# SENSOR_BOARD.net
KiCad netlist of a schematic drawn in Altium Designer
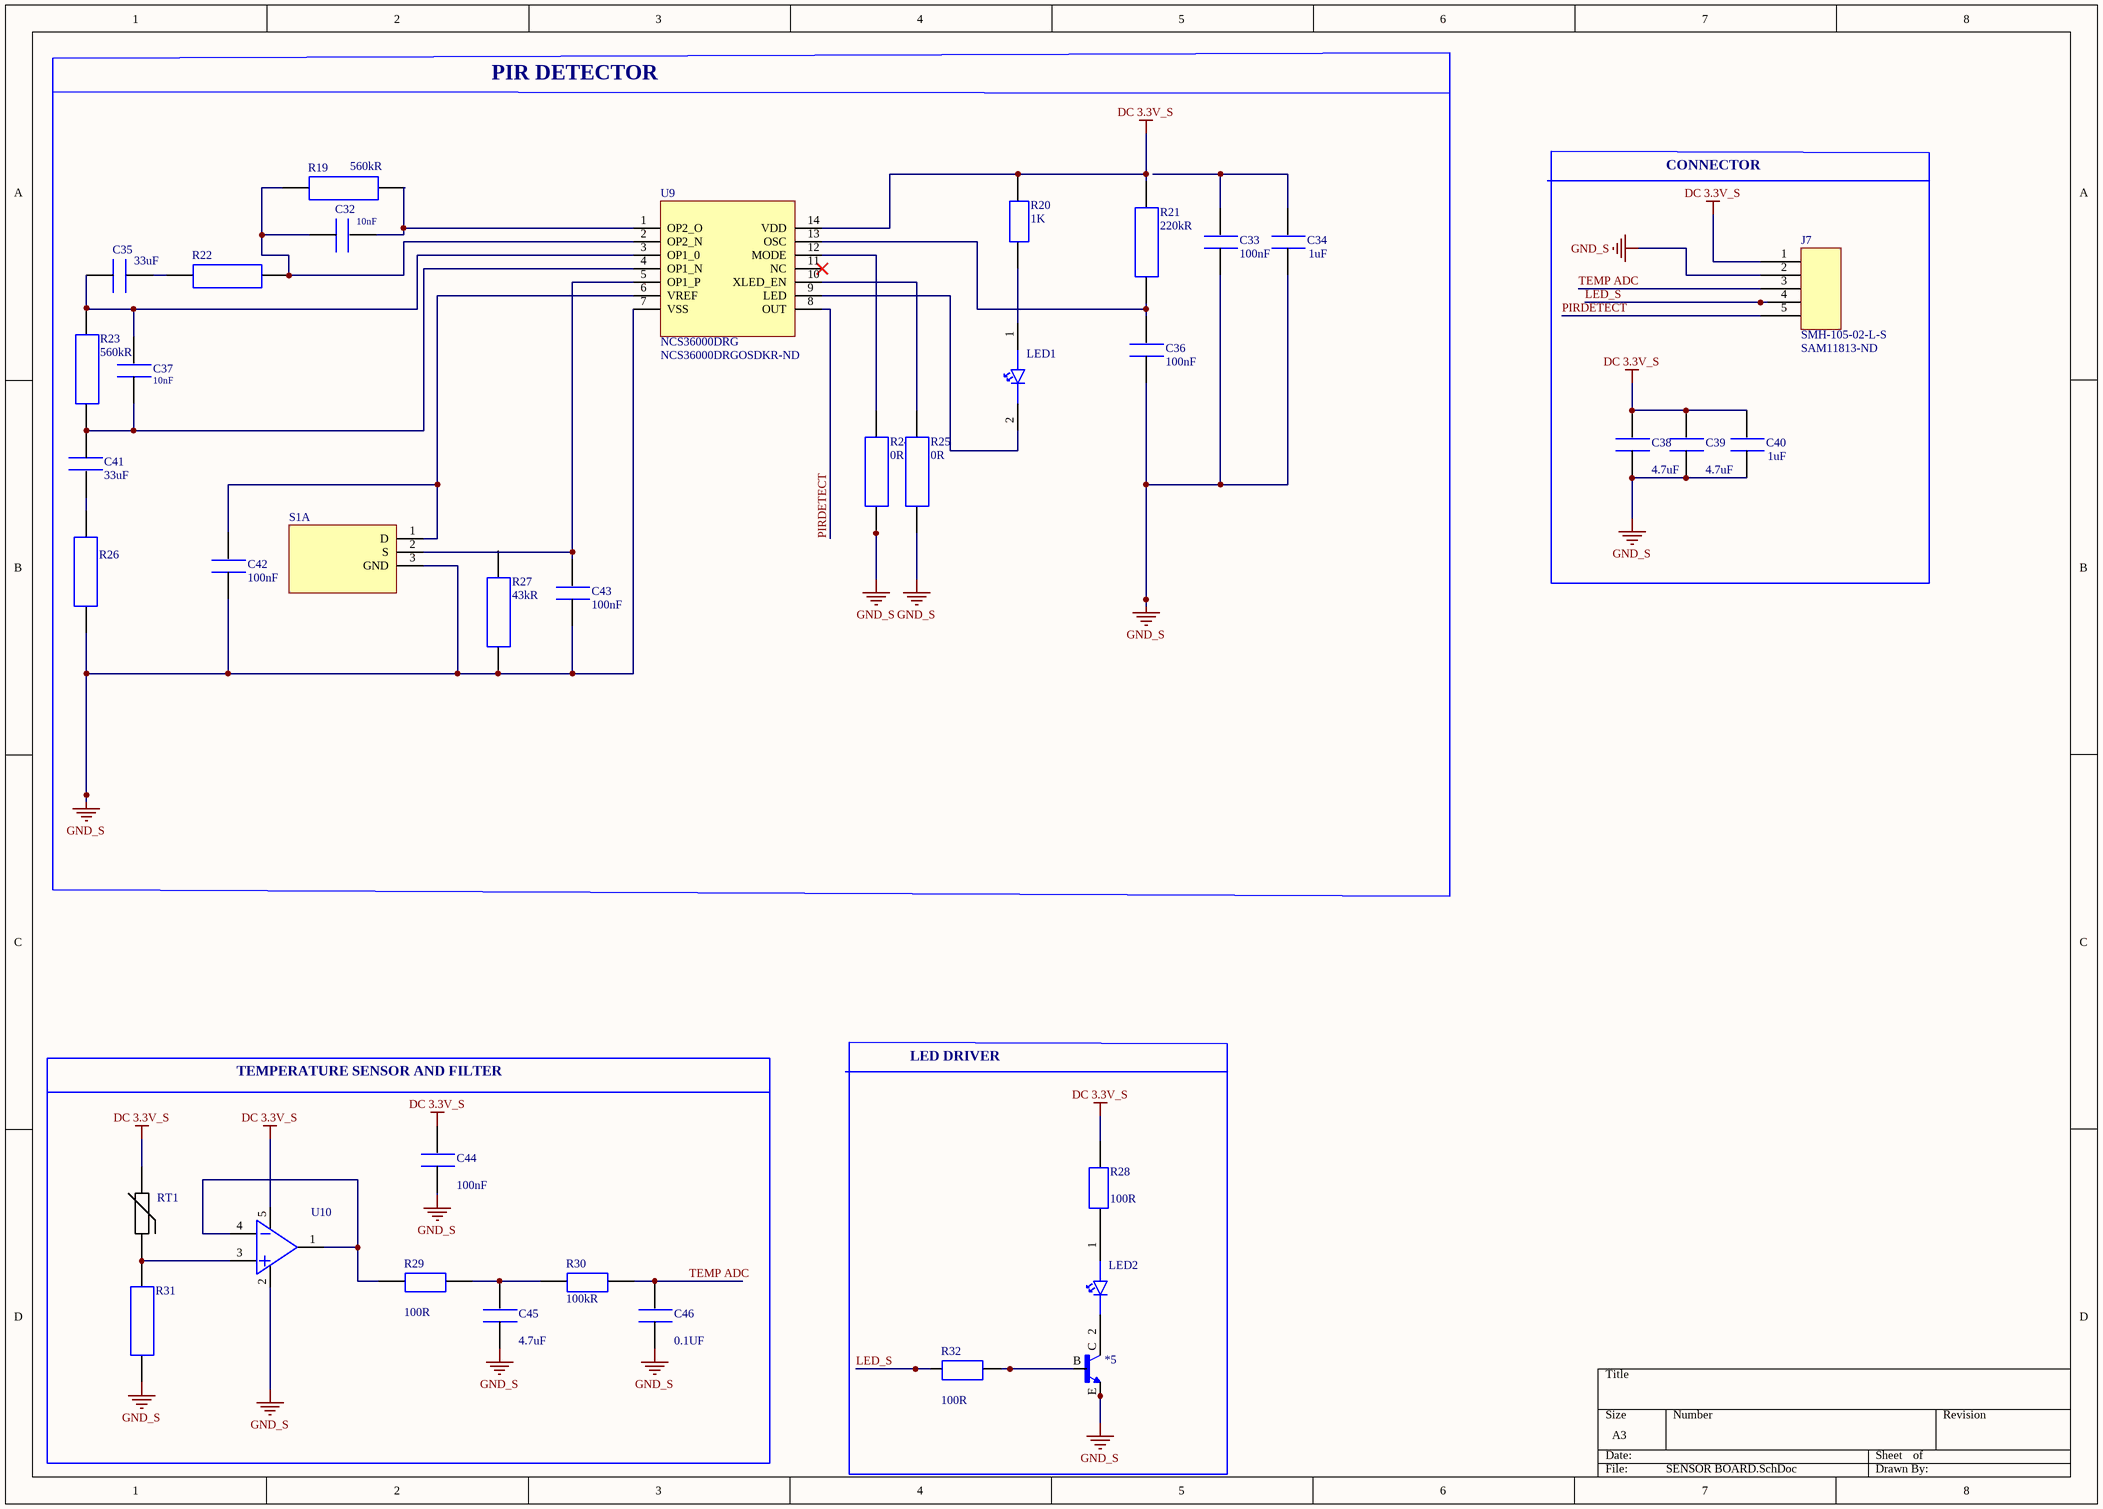
[diagram p0: SENSOR BOARD.SchDoc]

(export (version "E")
  (design (tool "Eeschema 10.0.6"))
  (components
    (comp (ref "*5")
      (value "MMBT3904-7-F")
      (footprint "SOT23_F")
      (description "Transistor General Purpose BJT NPN 40 Volt 0.2A Automotive 3-Pin SOT-23")
      (fields (field (name "MANUFACTURER") "Diodes Zetex"))
      (libsource (lib "ALTİUM_PROJE.Integrated_Library1") (part "TRANS NPN 40V 0.2A SMD SOT23-3"))
    )
    (comp (ref "C32")
      (value "0603B103K160CT")
      (footprint "CAP_0603")
      (description "CAP CER 0603 0.01 F, 10%,")
      (fields
        (field (name "MANUFACTURER") "Walsin Technologies")
        (field (name "TOLERANCE") "10%")
        (field (name "CAPACITANCE") "10nF")
      )
      (libsource (lib "ALTİUM_PROJE.Integrated_Library1") (part "CAP CER 10nF"))
    )
    (comp (ref "C33")
      (value "C0603C104K5RACTU")
      (footprint "CAP_0603")
      (description "CAP CEP 100nF %10 0603 SMD")
      (fields
        (field (name "MANUFACTURER") "KEMET")
        (field (name "TOLERANCE") "10%")
        (field (name "CAPACITANCE") "100nF")
      )
      (libsource (lib "ALTİUM_PROJE.Integrated_Library1") (part "CAP CEP 100nF 0603"))
    )
    (comp (ref "C34")
      (value "CL21B105KBFNNNE")
      (footprint "CAP 0805")
      (description "Ceramic capacitor SMD-0805      %10 1UF")
      (fields
        (field (name "MANUFACTURER") "Samsung")
        (field (name "TOLERANCE") "10%")
        (field (name "CAPACITANCE") "1uF")
      )
      (libsource (lib "ALTİUM_PROJE.Integrated_Library1") (part "CAP CER 1UF"))
    )
    (comp (ref "C35")
      (value "C3216X5R1E336M160AC")
      (footprint "CAP 1206")
      (description "C Series 1206 33 uF 25 V ±20 % Tolerance X5R SMT Multilayer Ceramic Capacitor")
      (fields
        (field (name "MANUFACTURER") "TDK")
        (field (name "TOLERANCE") "20%")
        (field (name "CAPACITANCE") "33uF")
      )
      (libsource (lib "ALTİUM_PROJE.Integrated_Library1") (part "CAP CER 33u F"))
    )
    (comp (ref "C36")
      (value "C0603C104K5RACTU")
      (footprint "CAP_0603")
      (description "CAP CEP 100nF %10 0603 SMD")
      (fields
        (field (name "MANUFACTURER") "KEMET")
        (field (name "TOLERANCE") "10%")
        (field (name "CAPACITANCE") "100nF")
      )
      (libsource (lib "ALTİUM_PROJE.Integrated_Library1") (part "CAP CEP 100nF 0603"))
    )
    (comp (ref "C37")
      (value "0603B103K160CT")
      (footprint "CAP_0603")
      (description "CAP CER 0603 0.01 F, 10%,")
      (fields
        (field (name "MANUFACTURER") "Walsin Technologies")
        (field (name "TOLERANCE") "10%")
        (field (name "CAPACITANCE") "10nF")
      )
      (libsource (lib "ALTİUM_PROJE.Integrated_Library1") (part "CAP CER 10nF"))
    )
    (comp (ref "C38")
      (value "CL21A475KAQNNNE")
      (footprint "CAP 0805")
      (description "Cap Cer 4.7uF %10 0805")
      (fields
        (field (name "MANUFACTURER") "Samsung")
        (field (name "TOLERANCE") "10%")
        (field (name "CAPACITANCE") "4.7uF")
      )
      (libsource (lib "ALTİUM_PROJE.Integrated_Library1") (part "CAP CER_0805"))
    )
    (comp (ref "C39")
      (value "CL21A475KAQNNNE")
      (footprint "CAP 0805")
      (description "Cap Cer 4.7uF %10 0805")
      (fields
        (field (name "MANUFACTURER") "Samsung")
        (field (name "TOLERANCE") "10%")
        (field (name "CAPACITANCE") "4.7uF")
      )
      (libsource (lib "ALTİUM_PROJE.Integrated_Library1") (part "CAP CER_0805"))
    )
    (comp (ref "C40")
      (value "CL21B105KBFNNNE")
      (footprint "CAP 0805")
      (description "Ceramic capacitor SMD-0805      %10 1UF")
      (fields
        (field (name "MANUFACTURER") "Samsung")
        (field (name "TOLERANCE") "10%")
        (field (name "CAPACITANCE") "1uF")
      )
      (libsource (lib "ALTİUM_PROJE.Integrated_Library1") (part "CAP CER 1UF"))
    )
    (comp (ref "C41")
      (value "C3216X5R1E336M160AC")
      (footprint "CAP 1206")
      (description "C Series 1206 33 uF 25 V ±20 % Tolerance X5R SMT Multilayer Ceramic Capacitor")
      (fields
        (field (name "MANUFACTURER") "TDK")
        (field (name "TOLERANCE") "20%")
        (field (name "CAPACITANCE") "33uF")
      )
      (libsource (lib "ALTİUM_PROJE.Integrated_Library1") (part "CAP CER 33u F"))
    )
    (comp (ref "C42")
      (value "C0603C104K5RACTU")
      (footprint "CAP_0603")
      (description "CAP CEP 100nF %10 0603 SMD")
      (fields
        (field (name "MANUFACTURER") "KEMET")
        (field (name "TOLERANCE") "10%")
        (field (name "CAPACITANCE") "100nF")
      )
      (libsource (lib "ALTİUM_PROJE.Integrated_Library1") (part "CAP CEP 100nF 0603"))
    )
    (comp (ref "C43")
      (value "C0603C104K5RACTU")
      (footprint "CAP_0603")
      (description "CAP CEP 100nF %10 0603 SMD")
      (fields
        (field (name "MANUFACTURER") "KEMET")
        (field (name "TOLERANCE") "10%")
        (field (name "CAPACITANCE") "100nF")
      )
      (libsource (lib "ALTİUM_PROJE.Integrated_Library1") (part "CAP CEP 100nF 0603"))
    )
    (comp (ref "C44")
      (value "C0603C104K5RACTU")
      (footprint "CAP_0603")
      (description "CAP CEP 100nF %10 0603 SMD")
      (fields
        (field (name "MANUFACTURER") "KEMET")
        (field (name "TOLERANCE") "10%")
        (field (name "CAPACITANCE") "100nF")
      )
      (libsource (lib "ALTİUM_PROJE.Integrated_Library1") (part "CAP CEP 100nF 0603"))
    )
    (comp (ref "C45")
      (value "CL21A475KAQNNNE")
      (footprint "CAP 0805")
      (description "Cap Cer 4.7uF %10 0805")
      (fields
        (field (name "MANUFACTURER") "Samsung")
        (field (name "TOLERANCE") "10%")
        (field (name "CAPACITANCE") "4.7uF")
      )
      (libsource (lib "ALTİUM_PROJE.Integrated_Library1") (part "CAP CER_0805"))
    )
    (comp (ref "C46")
      (value "CL21B104KBCNNNC")
      (footprint "CAP 0805")
      (description "Ceramic capacitor SMD-0805 100nF")
      (fields
        (field (name "MANUFACTURER") "Samsung")
        (field (name "TOLERANCE") "10%")
        (field (name "CAPACITANCE") "0.1UF")
      )
      (libsource (lib "ALTİUM_PROJE.Integrated_Library1") (part "CAP 0.1UF 0805"))
    )
    (comp (ref "J7")
      (value "SMH-105-02-L-S")
      (footprint "SMH-105")
      (description ".100 C.L. HORIZONTAL SMT SOCKET")
      (fields (field (name "MANUFACTURER") "Samtec") (field (name "SUPPLIER PART NUMBER 1") "SAM11813-ND"))
      (libsource (lib "ALTİUM_PROJE.Integrated_Library1") (part "PRO CONNECTER"))
    )
    (comp (ref "LED1")
      (value "LH R974-LP-1")
      (footprint "LED_RED_0805")
      (description "LED Uni-Color Hyper Red 660nm 2-Pin Chip 0805(2012Metric) T/R")
      (fields (field (name "MANUFACTURER") "Osram Opto"))
      (libsource (lib "ALTİUM_PROJE.Integrated_Library1") (part "LED_RED_0805"))
    )
    (comp (ref "LED2")
      (value "LH R974-LP-1")
      (footprint "LED_RED_0805")
      (description "LED Uni-Color Hyper Red 660nm 2-Pin Chip 0805(2012Metric) T/R")
      (fields (field (name "MANUFACTURER") "Osram Opto"))
      (libsource (lib "ALTİUM_PROJE.Integrated_Library1") (part "LED_RED_0805"))
    )
    (comp (ref "R19")
      (value "RC0603JR-07560KL")
      (footprint "RES_0603")
      (description "RES SMD 560K OHM 5% 1/10W 0603")
      (fields
        (field (name "MANUFACTURER") "Yageo")
        (field (name "TOLERANCE") "5%")
        (field (name "RESISTANCE") "560kR")
      )
      (libsource (lib "") (part "RES 560K OHM 5% 0603_1"))
    )
    (comp (ref "R20")
      (value "AC0603JR-101KL")
      (footprint "RES_0603")
      (description "Chip Resistor Automotive Grade Thick Film 0603 1kOhm 5% Paper T/R")
      (fields (field (name "MANUFACTURER") "Yageo") (field (name "RESISTOR") "1K"))
      (libsource (lib "ALTİUM_PROJE.Integrated_Library1") (part "RES 1K OHM"))
    )
    (comp (ref "R21")
      (value "RC0603JR-07220KL")
      (footprint "RES_0603")
      (description "Res Thick Film 0603 220K Ohm 5% 0.1W(1/10W) ±100ppm/C Pad SMD T/R")
      (fields
        (field (name "MANUFACTURER") "Yageo")
        (field (name "TOLERANCE") "5%")
        (field (name "RESISTANCE") "220kR")
      )
      (libsource (lib "ALTİUM_PROJE.Integrated_Library1") (part "RES 220K OHM 5%  0603"))
    )
    (comp (ref "R22")
      (value ":RC0603FR-0710KL")
      (footprint "RES_0603")
      (description "RES 10K %1 OHM 0603 SMD")
      (fields
        (field (name "MANUFACTURER") "Yageo")
        (field (name "MANUFACTURER PART NUMBER") "RC0603FR-0710KL")
      )
      (libsource (lib "") (part "RES 10K OHM 0603_1"))
    )
    (comp (ref "R23")
      (value "RC0603JR-07560KL")
      (footprint "RES_0603")
      (description "RES SMD 560K OHM 5% 1/10W 0603")
      (fields
        (field (name "MANUFACTURER") "Yageo")
        (field (name "TOLERANCE") "5%")
        (field (name "RESISTANCE") "560kR")
      )
      (libsource (lib "ALTİUM_PROJE.Integrated_Library1") (part "RES 560K OHM 5% 0603"))
    )
    (comp (ref "R24")
      (value "RC0603JR-070RL")
      (footprint "RES_0603")
      (description "RES SMD 0 OHM JUMPER 1/10W 0603")
      (fields
        (field (name "MANUFACTURER") "Yageo")
        (field (name "TOLERANCE") "1%")
        (field (name "RESISTANCE") "0R")
      )
      (libsource (lib "ALTİUM_PROJE.Integrated_Library1") (part "RES 0 %1 OHM 0603 SMD"))
    )
    (comp (ref "R25")
      (value "RC0603JR-070RL")
      (footprint "RES_0603")
      (description "RES SMD 0 OHM JUMPER 1/10W 0603")
      (fields
        (field (name "MANUFACTURER") "Yageo")
        (field (name "TOLERANCE") "1%")
        (field (name "RESISTANCE") "0R")
      )
      (libsource (lib "ALTİUM_PROJE.Integrated_Library1") (part "RES 0 %1 OHM 0603 SMD"))
    )
    (comp (ref "R26")
      (value ":RC0603FR-0710KL")
      (footprint "RES_0603")
      (description "RES 10K %1 OHM 0603 SMD")
      (fields
        (field (name "MANUFACTURER") "Yageo")
        (field (name "MANUFACTURER PART NUMBER") "RC0603FR-0710KL")
      )
      (libsource (lib "") (part "RES 10K OHM 0603_2"))
    )
    (comp (ref "R27")
      (value "RC0603JR-0743KL")
      (footprint "RES_0603")
      (description "Res Thick Film 0603 43K Ohm 5% 0.1W(1/10W) ±100ppm/°C Pad SMD T/R")
      (fields
        (field (name "MANUFACTURER") "Yageo")
        (field (name "TOLERANCE") "5%")
        (field (name "RESISTANCE") "43kR")
      )
      (libsource (lib "ALTİUM_PROJE.Integrated_Library1") (part "RES 43K OHM 5%  0603"))
    )
    (comp (ref "R28")
      (value "AC0603FR-10100RL")
      (footprint "RES_0603")
      (description "Chip Resistor Automotive Grade Thick Film 0603 100Ohm 1% Paper T/R")
      (fields
        (field (name "MANUFACTURER") "Yageo")
        (field (name "TOLERANCE") "1%")
        (field (name "RESISTANCE") "100R")
      )
      (libsource (lib "") (part "RES 100 OHM_1"))
    )
    (comp (ref "R29")
      (value "AC0603FR-10100RL")
      (footprint "RES_0603")
      (description "Chip Resistor Automotive Grade Thick Film 0603 100Ohm 1% Paper T/R")
      (fields
        (field (name "MANUFACTURER") "Yageo")
        (field (name "TOLERANCE") "1%")
        (field (name "RESISTANCE") "100R")
      )
      (libsource (lib "ALTİUM_PROJE.Integrated_Library1") (part "RES 100 OHM"))
    )
    (comp (ref "R30")
      (value "RE0603FRE07100KL")
      (footprint "RES_0603")
      (description "Res Thick Film 0603 100K Ohm 1% 1/10W ±50ppm/°C Molded SMD Paper T/R")
      (fields
        (field (name "MANUFACTURER") "Yageo")
        (field (name "TOLERANCE") "1%")
        (field (name "RESISTANCE") "100kR")
      )
      (libsource (lib "ALTİUM_PROJE.Integrated_Library1") (part "RES 100K OHM"))
    )
    (comp (ref "R31")
      (value ":RC0603FR-0710KL")
      (footprint "RES_0603")
      (description "RES 10K %1 OHM 0603 SMD")
      (fields
        (field (name "MANUFACTURER") "Yageo")
        (field (name "MANUFACTURER PART NUMBER") "RC0603FR-0710KL")
      )
      (libsource (lib "ALTİUM_PROJE.Integrated_Library1") (part "RES 10K OHM 0603"))
    )
    (comp (ref "R32")
      (value "AC0603FR-10100RL")
      (footprint "RES_0603")
      (description "Chip Resistor Automotive Grade Thick Film 0603 100Ohm 1% Paper T/R")
      (fields
        (field (name "MANUFACTURER") "Yageo")
        (field (name "TOLERANCE") "1%")
        (field (name "RESISTANCE") "100R")
      )
      (libsource (lib "ALTİUM_PROJE.Integrated_Library1") (part "RES 100 OHM"))
    )
    (comp (ref "RT1")
      (value "TFPT1206L1002FM")
      (footprint "RES_1206")
      (description "Thermistor PTC 10K Ohm 1% 2-Pin 1206 Surface Mount Solder Pad T/R Automotive")
      (fields (field (name "MANUFACTURER") "Vishay Dale") (field (name "TOLERANCE") "1%"))
      (libsource (lib "ALTİUM_PROJE.Integrated_Library1") (part "TFPT1206L1002FM"))
    )
    (comp (ref "S1")
      (value "LHI 878/3902")
      (footprint "LHI 878/3902")
      (description "SENSOR PYRO DETECTOR DUAL MOTION")
      (fields
        (field (name "MANUFACTURER") "Excelitas")
        (field (name "MANUFACTURER PART NUMBER") "LHI878/3902")
      )
      (libsource (lib "ALTİUM_PROJE.Integrated_Library1") (part "LHI 878/3902"))
    )
    (comp (ref "U9")
      (value "NCS36000DRG")
      (footprint "IC PIR")
      (description "NCS36000 Series Single 5.75V Passive Infrared Detector Controller (PIR) -SOIC-14")
      (fields
        (field (name "MANUFACTURER") "ON Semiconductor")
        (field (name "SUPPLIER PART NUMBER 1") "NCS36000DRGOSDKR-ND")
      )
      (libsource (lib "ALTİUM_PROJE.Integrated_Library1") (part "IC PIR DETECTOR CTLR 14SOIC"))
    )
    (comp (ref "U10")
      (value "OPA314AIDBVR")
      (footprint "OPAMP314")
      (description "OPA314 3MHZ, Low-power, Low-nois")
      (fields (field (name "MANUFACTURER") "Texas Instruments"))
      (libsource (lib "ALTİUM_PROJE.Integrated_Library1") (part "OPAMP 314"))
    )
  )
  (nets
    (net (code "1") (name "/LED_S") (class "Default")
      (node (ref "J7") (pin "4") (pinfunction "4_4") (pintype "passive"))
      (node (ref "R32") (pin "1") (pinfunction "24_1") (pintype "passive"))
    )
    (net (code "2") (name "/PIRDETECT") (class "Default")
      (node (ref "J7") (pin "5") (pinfunction "5_5") (pintype "passive"))
      (node (ref "U9") (pin "8") (pinfunction "OUT_8") (pintype "passive"))
    )
    (net (code "3") (name "/TEMP ADC") (class "Default")
      (node (ref "C46") (pin "2") (pinfunction "29_2") (pintype "passive"))
      (node (ref "J7") (pin "3") (pinfunction "3_3") (pintype "passive"))
      (node (ref "R30") (pin "2") (pinfunction "25_2") (pintype "passive"))
    )
    (net (code "4") (name "DC 3.3V_S") (class "Default")
      (node (ref "C38") (pin "2") (pinfunction "29_2") (pintype "passive"))
      (node (ref "C39") (pin "2") (pinfunction "29_2") (pintype "passive"))
      (node (ref "C40") (pin "2") (pinfunction "29_2") (pintype "passive"))
      (node (ref "C44") (pin "2") (pinfunction "29_2") (pintype "passive"))
      (node (ref "J7") (pin "1") (pinfunction "1_1") (pintype "passive"))
      (node (ref "R20") (pin "2") (pinfunction "25_2") (pintype "passive"))
      (node (ref "R21") (pin "2") (pinfunction "25_2") (pintype "passive"))
      (node (ref "R28") (pin "1") (pinfunction "24_1") (pintype "passive"))
      (node (ref "RT1") (pin "1") (pinfunction "1_1") (pintype "passive"))
      (node (ref "U10") (pin "5") (pinfunction "OUT_5") (pintype "passive"))
      (node (ref "U9") (pin "14") (pinfunction "VDD_14") (pintype "passive"))
    )
    (net (code "5") (name "GND_S") (class "Default")
      (node (ref "*5") (pin "E") (pinfunction "E_E") (pintype "passive"))
      (node (ref "C33") (pin "1") (pinfunction "28_1") (pintype "passive"))
      (node (ref "C34") (pin "1") (pinfunction "28_1") (pintype "passive"))
      (node (ref "C36") (pin "1") (pinfunction "28_1") (pintype "passive"))
      (node (ref "C38") (pin "1") (pinfunction "28_1") (pintype "passive"))
      (node (ref "C39") (pin "1") (pinfunction "28_1") (pintype "passive"))
      (node (ref "C40") (pin "1") (pinfunction "28_1") (pintype "passive"))
      (node (ref "C42") (pin "1") (pinfunction "28_1") (pintype "passive"))
      (node (ref "C43") (pin "1") (pinfunction "28_1") (pintype "passive"))
      (node (ref "C44") (pin "1") (pinfunction "28_1") (pintype "passive"))
      (node (ref "C45") (pin "1") (pinfunction "28_1") (pintype "passive"))
      (node (ref "C46") (pin "1") (pinfunction "28_1") (pintype "passive"))
      (node (ref "J7") (pin "2") (pinfunction "2_2") (pintype "passive"))
      (node (ref "R24") (pin "1") (pinfunction "24_1") (pintype "passive"))
      (node (ref "R25") (pin "1") (pinfunction "24_1") (pintype "passive"))
      (node (ref "R26") (pin "2") (pinfunction "25_2") (pintype "passive"))
      (node (ref "R27") (pin "1") (pinfunction "24_1") (pintype "passive"))
      (node (ref "R31") (pin "1") (pinfunction "24_1") (pintype "passive"))
      (node (ref "S1") (pin "3") (pinfunction "GND_3") (pintype "passive"))
      (node (ref "U10") (pin "2") (pintype "passive"))
      (node (ref "U9") (pin "7") (pinfunction "VSS_7") (pintype "passive"))
    )
    (net (code "6") (name "Net-(C32-28)") (class "Default")
      (node (ref "C32") (pin "1") (pinfunction "28_1") (pintype "passive"))
      (node (ref "R19") (pin "1") (pinfunction "24_1") (pintype "passive"))
      (node (ref "R22") (pin "2") (pinfunction "25_2") (pintype "passive"))
      (node (ref "U9") (pin "2") (pinfunction "OP2_N_2") (pintype "passive"))
    )
    (net (code "7") (name "Net-(C32-29)") (class "Default")
      (node (ref "C32") (pin "2") (pinfunction "29_2") (pintype "passive"))
      (node (ref "R19") (pin "2") (pinfunction "2_2") (pintype "passive"))
      (node (ref "U9") (pin "1") (pinfunction "OP2_O_1") (pintype "passive"))
    )
    (net (code "8") (name "Net-(C33-29)") (class "Default")
      (node (ref "C33") (pin "2") (pinfunction "29_2") (pintype "passive"))
      (node (ref "C34") (pin "2") (pinfunction "29_2") (pintype "passive"))
    )
    (net (code "9") (name "Net-(C35-28)") (class "Default")
      (node (ref "C35") (pin "1") (pinfunction "28_1") (pintype "passive"))
      (node (ref "C37") (pin "2") (pinfunction "29_2") (pintype "passive"))
      (node (ref "R23") (pin "2") (pinfunction "2_2") (pintype "passive"))
      (node (ref "U9") (pin "3") (pinfunction "OP1_0_3") (pintype "passive"))
    )
    (net (code "10") (name "Net-(C35-29)") (class "Default")
      (node (ref "C35") (pin "2") (pinfunction "29_2") (pintype "passive"))
      (node (ref "R22") (pin "1") (pinfunction "24_1") (pintype "passive"))
    )
    (net (code "11") (name "Net-(C36-29)") (class "Default")
      (node (ref "C36") (pin "2") (pinfunction "29_2") (pintype "passive"))
      (node (ref "R21") (pin "1") (pinfunction "24_1") (pintype "passive"))
      (node (ref "U9") (pin "13") (pinfunction "OSC_13") (pintype "passive"))
    )
    (net (code "12") (name "Net-(C37-28)") (class "Default")
      (node (ref "C37") (pin "1") (pinfunction "28_1") (pintype "passive"))
      (node (ref "C41") (pin "1") (pinfunction "28_1") (pintype "passive"))
      (node (ref "R23") (pin "1") (pinfunction "24_1") (pintype "passive"))
      (node (ref "U9") (pin "4") (pinfunction "OP1_N_4") (pintype "passive"))
    )
    (net (code "13") (name "Net-(C41-29)") (class "Default")
      (node (ref "C41") (pin "2") (pinfunction "29_2") (pintype "passive"))
      (node (ref "R26") (pin "1") (pinfunction "24_1") (pintype "passive"))
    )
    (net (code "14") (name "Net-(C42-29)") (class "Default")
      (node (ref "C42") (pin "2") (pinfunction "29_2") (pintype "passive"))
      (node (ref "S1") (pin "1") (pinfunction "D_1") (pintype "passive"))
      (node (ref "U9") (pin "6") (pinfunction "VREF_6") (pintype "passive"))
    )
    (net (code "15") (name "Net-(C43-29)") (class "Default")
      (node (ref "C43") (pin "2") (pinfunction "29_2") (pintype "passive"))
      (node (ref "S1") (pin "2") (pinfunction "S_2") (pintype "passive"))
      (node (ref "U9") (pin "5") (pinfunction "OP1_P_5") (pintype "passive"))
    )
    (net (code "16") (name "Net-(C45-29)") (class "Default")
      (node (ref "C45") (pin "2") (pinfunction "29_2") (pintype "passive"))
      (node (ref "R29") (pin "2") (pinfunction "25_2") (pintype "passive"))
      (node (ref "R30") (pin "1") (pinfunction "24_1") (pintype "passive"))
    )
    (net (code "17") (name "Net-(LED1-ANOT)") (class "Default")
      (node (ref "LED1") (pin "1") (pinfunction "ANOT_1") (pintype "passive"))
      (node (ref "R20") (pin "1") (pinfunction "24_1") (pintype "passive"))
    )
    (net (code "18") (name "Net-(LED1-CAOTHODE)") (class "Default")
      (node (ref "LED1") (pin "2") (pinfunction "CAOTHODE_2") (pintype "passive"))
      (node (ref "U9") (pin "9") (pinfunction "LED_9") (pintype "passive"))
    )
    (net (code "19") (name "Net-(LED2-CAOTHODE)") (class "Default")
      (node (ref "*5") (pin "C") (pinfunction "C_C") (pintype "passive"))
      (node (ref "LED2") (pin "2") (pinfunction "CAOTHODE_2") (pintype "passive"))
    )
    (net (code "20") (name "Net-(R24-25)") (class "Default")
      (node (ref "R24") (pin "2") (pinfunction "25_2") (pintype "passive"))
      (node (ref "U9") (pin "12") (pinfunction "MODE_12") (pintype "passive"))
    )
    (net (code "21") (name "Net-(R25-25)") (class "Default")
      (node (ref "R25") (pin "2") (pinfunction "25_2") (pintype "passive"))
      (node (ref "U9") (pin "10") (pinfunction "XLED_EN_10") (pintype "passive"))
    )
    (net (code "22") (name "Net-(R29-24)") (class "Default")
      (node (ref "R29") (pin "1") (pinfunction "24_1") (pintype "passive"))
      (node (ref "U10") (pin "1") (pinfunction "OUT_1") (pintype "passive"))
      (node (ref "U10") (pin "4") (pinfunction "OUT_4") (pintype "passive"))
    )
    (net (code "23") (name "Net-(R31-25)") (class "Default")
      (node (ref "R31") (pin "2") (pinfunction "25_2") (pintype "passive"))
      (node (ref "RT1") (pin "2") (pinfunction "2_2") (pintype "passive"))
      (node (ref "U10") (pin "3") (pinfunction "OUT_3") (pintype "passive"))
    )
    (net (code "24") (name "Net-(R32-25)") (class "Default")
      (node (ref "*5") (pin "B") (pinfunction "B_B") (pintype "passive"))
      (node (ref "R32") (pin "2") (pinfunction "25_2") (pintype "passive"))
    )
    (net (code "25") (name "unconnected-(LED2-ANOT-Pad1)") (class "Default")
      (node (ref "LED2") (pin "1") (pinfunction "ANOT_1") (pintype "passive"))
    )
    (net (code "26") (name "unconnected-(R27-25-Pad2)") (class "Default")
      (node (ref "R27") (pin "2") (pinfunction "25_2") (pintype "passive"))
    )
    (net (code "27") (name "unconnected-(R28-25-Pad2)") (class "Default")
      (node (ref "R28") (pin "2") (pinfunction "25_2") (pintype "passive"))
    )
    (net (code "28") (name "unconnected-(U9-NC-Pad11)") (class "Default")
      (node (ref "U9") (pin "11") (pinfunction "NC_11") (pintype "passive+no_connect"))
    )
  )
)
